# On_Board_Computer.net
KiCad netlist of a schematic drawn in EAGLE
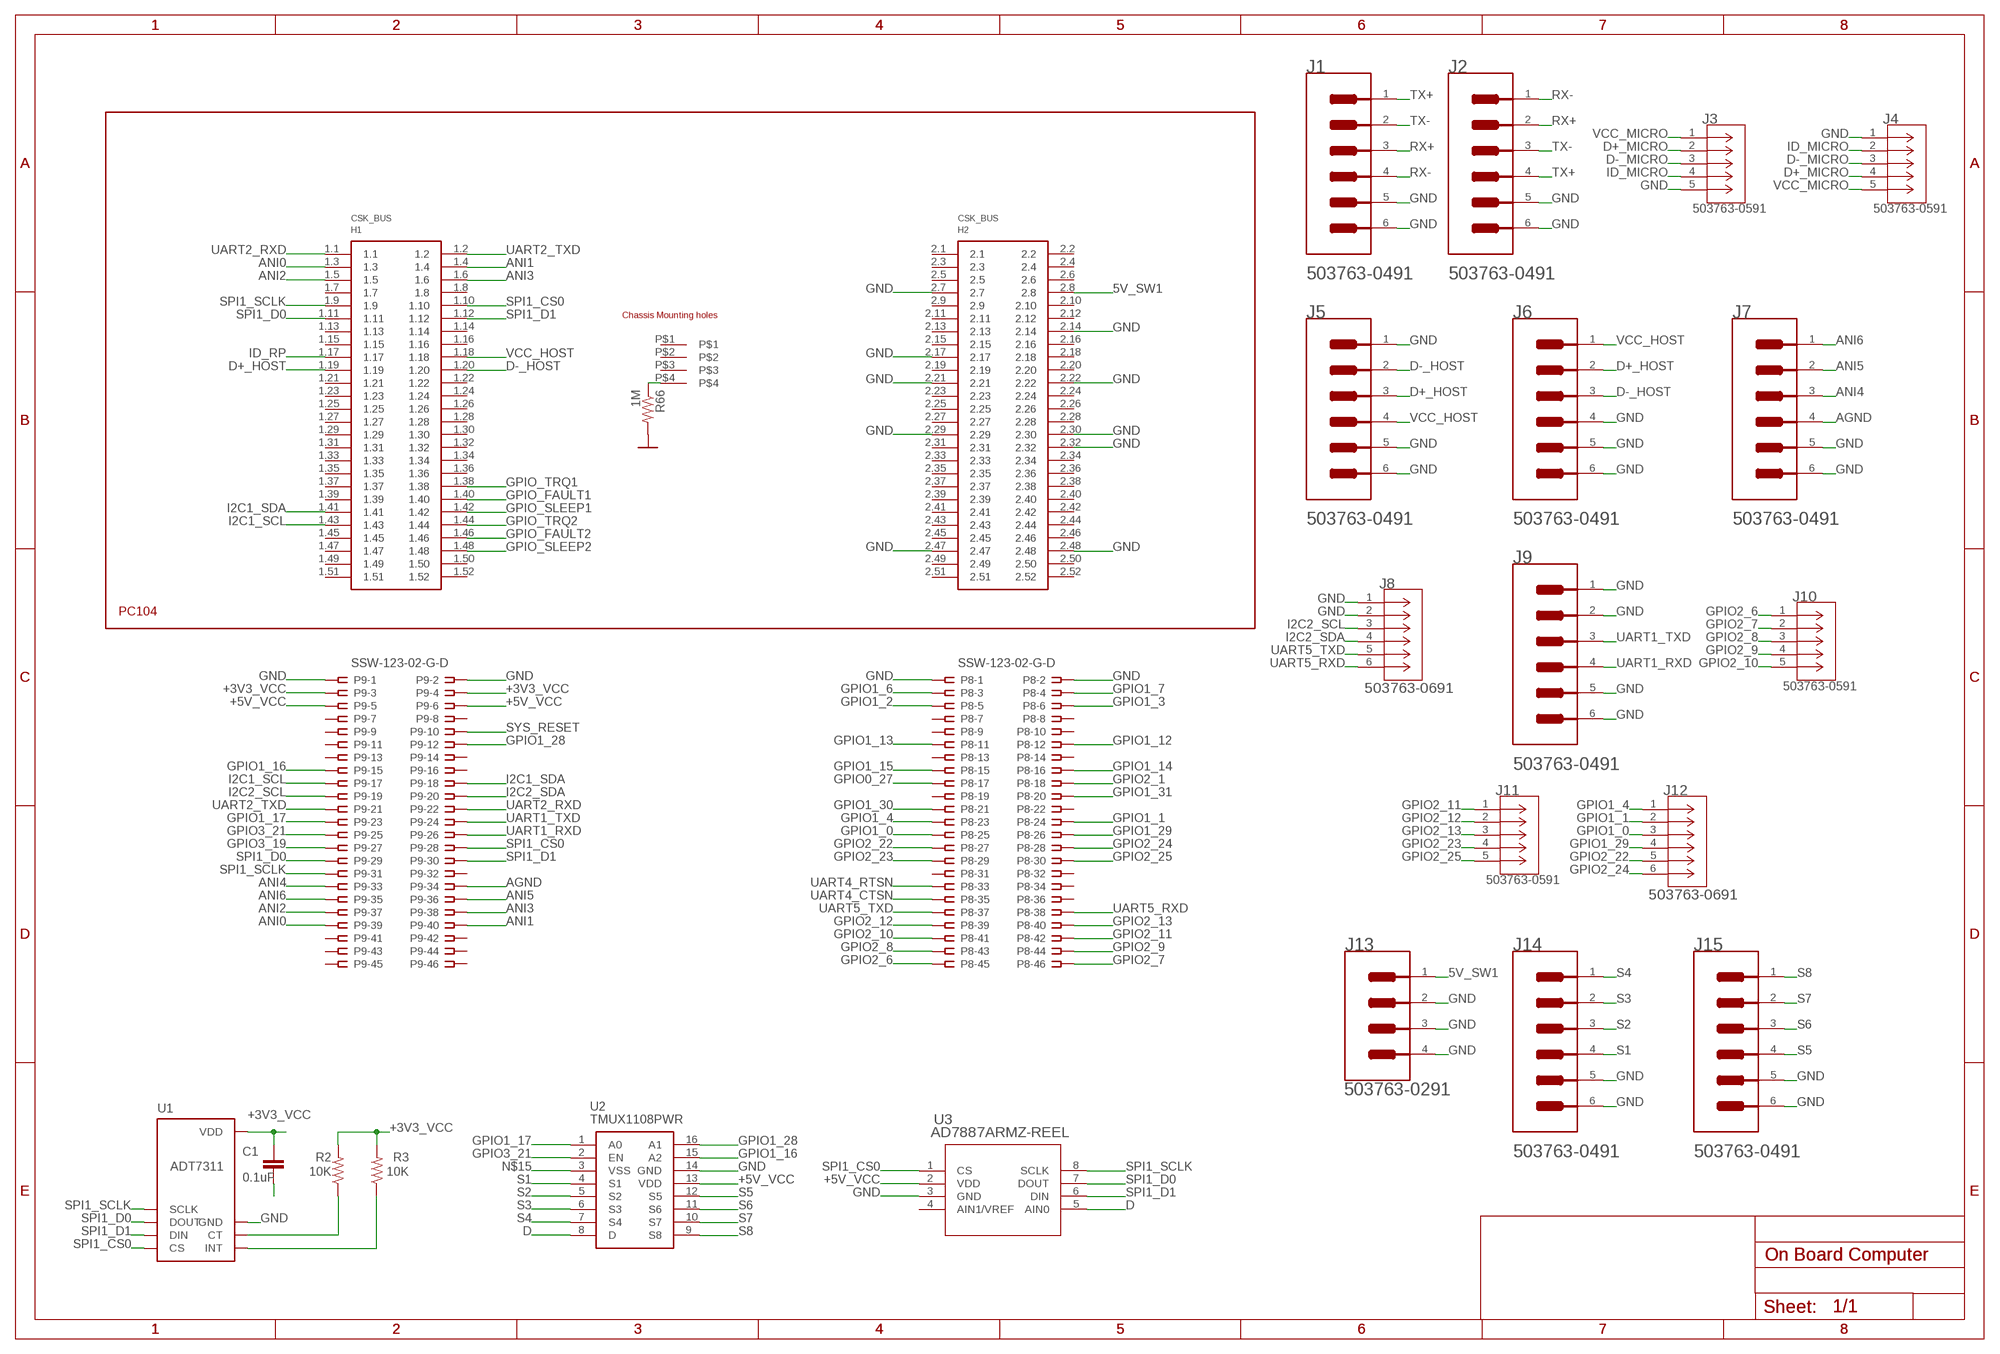
[diagram p0: schematic, sheet 1]

(export (version "E")
  (design (tool "Eeschema 10.0.6"))
  (components
    (comp (ref "C1")
      (value "0.1uF")
      (footprint "eagle-import:0805")
      (libsource (lib "eagle-import") (part "CAP0805"))
    )
    (comp (ref "H1")
      (value "PC104_WCONN")
      (footprint "eagle-import:PC104_WCONN")
      (libsource (lib "eagle-import") (part "PC104_WCONN"))
    )
    (comp (ref "J1")
      (value "MOLEX_503763-0491MOLEX_503763-0491_0_0")
      (footprint "eagle-import:MOLEX_503763-0491_0")
      (fields
        (field (name "DIGIKEY_PART_NUMBER") "WM10655CT-ND")
        (field (name "MF") "Molex")
        (field (name "MOUSER_PART_NUMBER") "538-503763-0491")
      )
      (libsource (lib "eagle-import") (part "MOLEX_503763-0491MOLEX_503763-0491_0_0"))
    )
    (comp (ref "J2")
      (value "MOLEX_503763-0491MOLEX_503763-0491_0_0")
      (footprint "eagle-import:MOLEX_503763-0491_0")
      (fields
        (field (name "DIGIKEY_PART_NUMBER") "WM10655CT-ND")
        (field (name "MF") "Molex")
        (field (name "MOUSER_PART_NUMBER") "538-503763-0491")
      )
      (libsource (lib "eagle-import") (part "MOLEX_503763-0491MOLEX_503763-0491_0_0"))
    )
    (comp (ref "J3")
      (value "503763-0591")
      (footprint "eagle-import:CONN_5037630591_MOL")
      (fields (field (name "COPYRIGHT") "Copyright (C) 2018 Accelerated Designs. All rights reserved"))
      (libsource (lib "eagle-import") (part "503763-0591"))
    )
    (comp (ref "J4")
      (value "503763-0591")
      (footprint "eagle-import:CONN_5037630591_MOL")
      (fields (field (name "COPYRIGHT") "Copyright (C) 2018 Accelerated Designs. All rights reserved"))
      (libsource (lib "eagle-import") (part "503763-0591"))
    )
    (comp (ref "J5")
      (value "MOLEX_503763-0491MOLEX_503763-0491_0_0")
      (footprint "eagle-import:MOLEX_503763-0491_0")
      (fields
        (field (name "DIGIKEY_PART_NUMBER") "WM10655CT-ND")
        (field (name "MF") "Molex")
        (field (name "MOUSER_PART_NUMBER") "538-503763-0491")
      )
      (libsource (lib "eagle-import") (part "MOLEX_503763-0491MOLEX_503763-0491_0_0"))
    )
    (comp (ref "J6")
      (value "MOLEX_503763-0491MOLEX_503763-0491_0_0")
      (footprint "eagle-import:MOLEX_503763-0491_0")
      (fields
        (field (name "DIGIKEY_PART_NUMBER") "WM10655CT-ND")
        (field (name "MF") "Molex")
        (field (name "MOUSER_PART_NUMBER") "538-503763-0491")
      )
      (libsource (lib "eagle-import") (part "MOLEX_503763-0491MOLEX_503763-0491_0_0"))
    )
    (comp (ref "J7")
      (value "MOLEX_503763-0491MOLEX_503763-0491_0_0")
      (footprint "eagle-import:MOLEX_503763-0491_0")
      (fields
        (field (name "DIGIKEY_PART_NUMBER") "WM10655CT-ND")
        (field (name "MF") "Molex")
        (field (name "MOUSER_PART_NUMBER") "538-503763-0491")
      )
      (libsource (lib "eagle-import") (part "MOLEX_503763-0491MOLEX_503763-0491_0_0"))
    )
    (comp (ref "J8")
      (value "503763-0691")
      (footprint "eagle-import:CONN_503763-0691_MOL")
      (fields (field (name "COPYRIGHT") "Copyright (C) 2018 Accelerated Designs. All rights reserved"))
      (libsource (lib "eagle-import") (part "503763-0691"))
    )
    (comp (ref "J9")
      (value "MOLEX_503763-0491MOLEX_503763-0491_0_0")
      (footprint "eagle-import:MOLEX_503763-0491_0")
      (fields
        (field (name "DIGIKEY_PART_NUMBER") "WM10655CT-ND")
        (field (name "MF") "Molex")
        (field (name "MOUSER_PART_NUMBER") "538-503763-0491")
      )
      (libsource (lib "eagle-import") (part "MOLEX_503763-0491MOLEX_503763-0491_0_0"))
    )
    (comp (ref "J10")
      (value "503763-0591")
      (footprint "eagle-import:CONN_5037630591_MOL")
      (fields (field (name "COPYRIGHT") "Copyright (C) 2018 Accelerated Designs. All rights reserved"))
      (libsource (lib "eagle-import") (part "503763-0591"))
    )
    (comp (ref "J11")
      (value "503763-0591")
      (footprint "eagle-import:CONN_5037630591_MOL")
      (fields (field (name "COPYRIGHT") "Copyright (C) 2018 Accelerated Designs. All rights reserved"))
      (libsource (lib "eagle-import") (part "503763-0591"))
    )
    (comp (ref "J12")
      (value "503763-0691")
      (footprint "eagle-import:CONN_503763-0691_MOL")
      (fields (field (name "COPYRIGHT") "Copyright (C) 2018 Accelerated Designs. All rights reserved"))
      (libsource (lib "eagle-import") (part "503763-0691"))
    )
    (comp (ref "J13")
      (value "MOLEX_503763-0291MOLEX_503763-0291_0_0")
      (footprint "eagle-import:MOLEX_503763-0291_0")
      (fields
        (field (name "DIGIKEY_PART_NUMBER") "WM10654CT-ND")
        (field (name "MF") "Molex")
        (field (name "MOUSER_PART_NUMBER") "538-503763-0291")
      )
      (libsource (lib "eagle-import") (part "MOLEX_503763-0291MOLEX_503763-0291_0_0"))
    )
    (comp (ref "J14")
      (value "MOLEX_503763-0491MOLEX_503763-0491_0_0")
      (footprint "eagle-import:MOLEX_503763-0491_0")
      (fields
        (field (name "DIGIKEY_PART_NUMBER") "WM10655CT-ND")
        (field (name "MF") "Molex")
        (field (name "MOUSER_PART_NUMBER") "538-503763-0491")
      )
      (libsource (lib "eagle-import") (part "MOLEX_503763-0491MOLEX_503763-0491_0_0"))
    )
    (comp (ref "J15")
      (value "MOLEX_503763-0491MOLEX_503763-0491_0_0")
      (footprint "eagle-import:MOLEX_503763-0491_0")
      (fields
        (field (name "DIGIKEY_PART_NUMBER") "WM10655CT-ND")
        (field (name "MF") "Molex")
        (field (name "MOUSER_PART_NUMBER") "538-503763-0491")
      )
      (libsource (lib "eagle-import") (part "MOLEX_503763-0491MOLEX_503763-0491_0_0"))
    )
    (comp (ref "P8")
      (value "SSW-123-02-G-D")
      (footprint "eagle-import:SSW-123-02-G-D")
      (fields (field (name "MF") "Samtec Inc."))
      (libsource (lib "eagle-import") (part "SSW-123-02-G-D"))
    )
    (comp (ref "P9")
      (value "SSW-123-02-G-D")
      (footprint "eagle-import:SSW-123-02-G-D")
      (fields (field (name "MF") "Samtec Inc."))
      (libsource (lib "eagle-import") (part "SSW-123-02-G-D"))
    )
    (comp (ref "R2")
      (value "10K")
      (footprint "eagle-import:0805")
      (libsource (lib "eagle-import") (part "RESISTOR0805-RES"))
    )
    (comp (ref "R3")
      (value "10K")
      (footprint "eagle-import:0805")
      (libsource (lib "eagle-import") (part "RESISTOR0805-RES"))
    )
    (comp (ref "R66")
      (value "1M")
      (footprint "eagle-import:0805")
      (libsource (lib "eagle-import") (part "RESISTOR0805-RES"))
    )
    (comp (ref "U1")
      (value "ADT7311")
      (footprint "eagle-import:SOIC-8")
      (libsource (lib "eagle-import") (part "ADT7311"))
    )
    (comp (ref "U2")
      (value "TMUX1108PWR")
      (footprint "eagle-import:SOP65P640X120-16N")
      (fields (field (name "MOUSER_PART_NUMBER") "595-TMUX1108PWR"))
      (libsource (lib "eagle-import") (part "TMUX1108PWR"))
    )
    (comp (ref "U3")
      (value "AD7887ARMZ-REEL")
      (footprint "eagle-import:RM_8_ADI")
      (libsource (lib "eagle-import") (part "AD7887ARMZ-REEL"))
    )
  )
  (nets
    (net (code "1") (name "/+3V3_VCC") (class "Default")
      (node (ref "C1") (pin "1") (pinfunction "1_1") (pintype "passive"))
      (node (ref "P9") (pin "3") (pinfunction "1_3") (pintype "passive"))
      (node (ref "P9") (pin "4") (pinfunction "1_4") (pintype "passive"))
      (node (ref "R2") (pin "2") (pinfunction "2_2") (pintype "passive"))
      (node (ref "R3") (pin "2") (pinfunction "2_2") (pintype "passive"))
      (node (ref "U1") (pin "8") (pinfunction "VDD_8") (pintype "bidirectional"))
    )
    (net (code "2") (name "/+5V_VCC") (class "Default")
      (node (ref "P9") (pin "5") (pinfunction "1_5") (pintype "passive"))
      (node (ref "P9") (pin "6") (pinfunction "1_6") (pintype "passive"))
      (node (ref "U2") (pin "13") (pinfunction "VDD_13") (pintype "bidirectional"))
      (node (ref "U3") (pin "2") (pinfunction "VDD_2") (pintype "power_in"))
    )
    (net (code "3") (name "/5V_SW1") (class "Default")
      (node (ref "H1") (pin "2.8") (pinfunction "2.8_2.8") (pintype "bidirectional"))
      (node (ref "J13") (pin "1") (pinfunction "1_1") (pintype "bidirectional"))
    )
    (net (code "4") (name "/AGND") (class "Default")
      (node (ref "J7") (pin "4") (pinfunction "4_4") (pintype "passive"))
      (node (ref "P9") (pin "34") (pinfunction "1_34") (pintype "passive"))
    )
    (net (code "5") (name "/ANI0") (class "Default")
      (node (ref "H1") (pin "1.3") (pinfunction "1.3_1.3") (pintype "bidirectional"))
      (node (ref "P9") (pin "39") (pinfunction "1_39") (pintype "passive"))
    )
    (net (code "6") (name "/ANI1") (class "Default")
      (node (ref "H1") (pin "1.4") (pinfunction "1.4_1.4") (pintype "bidirectional"))
      (node (ref "P9") (pin "40") (pinfunction "1_40") (pintype "passive"))
    )
    (net (code "7") (name "/ANI2") (class "Default")
      (node (ref "H1") (pin "1.5") (pinfunction "1.5_1.5") (pintype "bidirectional"))
      (node (ref "P9") (pin "37") (pinfunction "1_37") (pintype "passive"))
    )
    (net (code "8") (name "/ANI3") (class "Default")
      (node (ref "H1") (pin "1.6") (pinfunction "1.6_1.6") (pintype "bidirectional"))
      (node (ref "P9") (pin "38") (pinfunction "1_38") (pintype "passive"))
    )
    (net (code "9") (name "/ANI4") (class "Default")
      (node (ref "J7") (pin "3") (pinfunction "3_3") (pintype "passive"))
      (node (ref "P9") (pin "33") (pinfunction "1_33") (pintype "passive"))
    )
    (net (code "10") (name "/ANI5") (class "Default")
      (node (ref "J7") (pin "2") (pinfunction "2_2") (pintype "passive"))
      (node (ref "P9") (pin "36") (pinfunction "1_36") (pintype "passive"))
    )
    (net (code "11") (name "/ANI6") (class "Default")
      (node (ref "J7") (pin "1") (pinfunction "1_1") (pintype "passive"))
      (node (ref "P9") (pin "35") (pinfunction "1_35") (pintype "passive"))
    )
    (net (code "12") (name "/D") (class "Default")
      (node (ref "U2") (pin "8") (pinfunction "D_8") (pintype "bidirectional"))
      (node (ref "U3") (pin "5") (pinfunction "AIN0_5") (pintype "passive"))
    )
    (net (code "13") (name "/D+_HOST") (class "Default")
      (node (ref "H1") (pin "1.19") (pinfunction "1.19_1.19") (pintype "bidirectional"))
      (node (ref "J5") (pin "3") (pinfunction "3_3") (pintype "passive"))
      (node (ref "J6") (pin "2") (pinfunction "2_2") (pintype "passive"))
    )
    (net (code "14") (name "/D+_MICRO") (class "Default")
      (node (ref "J3") (pin "2") (pinfunction "2_2") (pintype "passive"))
      (node (ref "J4") (pin "4") (pinfunction "4_4") (pintype "passive"))
    )
    (net (code "15") (name "/D-_HOST") (class "Default")
      (node (ref "H1") (pin "1.20") (pinfunction "1.20_1.20") (pintype "bidirectional"))
      (node (ref "J5") (pin "2") (pinfunction "2_2") (pintype "passive"))
      (node (ref "J6") (pin "3") (pinfunction "3_3") (pintype "passive"))
    )
    (net (code "16") (name "/D-_MICRO") (class "Default")
      (node (ref "J3") (pin "3") (pinfunction "3_3") (pintype "passive"))
      (node (ref "J4") (pin "3") (pinfunction "3_3") (pintype "passive"))
    )
    (net (code "17") (name "/GPIO0_27") (class "Default")
      (node (ref "P8") (pin "17") (pinfunction "1_17") (pintype "passive"))
    )
    (net (code "18") (name "/GPIO1_0") (class "Default")
      (node (ref "J12") (pin "3") (pinfunction "3_3") (pintype "passive"))
      (node (ref "P8") (pin "25") (pinfunction "1_25") (pintype "passive"))
    )
    (net (code "19") (name "/GPIO1_1") (class "Default")
      (node (ref "J12") (pin "2") (pinfunction "2_2") (pintype "passive"))
      (node (ref "P8") (pin "24") (pinfunction "1_24") (pintype "passive"))
    )
    (net (code "20") (name "/GPIO1_2") (class "Default")
      (node (ref "P8") (pin "5") (pinfunction "1_5") (pintype "passive"))
    )
    (net (code "21") (name "/GPIO1_3") (class "Default")
      (node (ref "P8") (pin "6") (pinfunction "1_6") (pintype "passive"))
    )
    (net (code "22") (name "/GPIO1_4") (class "Default")
      (node (ref "J12") (pin "1") (pinfunction "1_1") (pintype "passive"))
      (node (ref "P8") (pin "23") (pinfunction "1_23") (pintype "passive"))
    )
    (net (code "23") (name "/GPIO1_6") (class "Default")
      (node (ref "P8") (pin "3") (pinfunction "1_3") (pintype "passive"))
    )
    (net (code "24") (name "/GPIO1_7") (class "Default")
      (node (ref "P8") (pin "4") (pinfunction "1_4") (pintype "passive"))
    )
    (net (code "25") (name "/GPIO1_12") (class "Default")
      (node (ref "P8") (pin "12") (pinfunction "1_12") (pintype "passive"))
    )
    (net (code "26") (name "/GPIO1_13") (class "Default")
      (node (ref "P8") (pin "11") (pinfunction "1_11") (pintype "passive"))
    )
    (net (code "27") (name "/GPIO1_14") (class "Default")
      (node (ref "P8") (pin "16") (pinfunction "1_16") (pintype "passive"))
    )
    (net (code "28") (name "/GPIO1_15") (class "Default")
      (node (ref "P8") (pin "15") (pinfunction "1_15") (pintype "passive"))
    )
    (net (code "29") (name "/GPIO1_16") (class "Default")
      (node (ref "P9") (pin "15") (pinfunction "1_15") (pintype "passive"))
      (node (ref "U2") (pin "15") (pinfunction "A2_15") (pintype "bidirectional"))
    )
    (net (code "30") (name "/GPIO1_17") (class "Default")
      (node (ref "P9") (pin "23") (pinfunction "1_23") (pintype "passive"))
      (node (ref "U2") (pin "1") (pinfunction "A0_1") (pintype "bidirectional"))
    )
    (net (code "31") (name "/GPIO1_28") (class "Default")
      (node (ref "P9") (pin "12") (pinfunction "1_12") (pintype "passive"))
      (node (ref "U2") (pin "16") (pinfunction "A1_16") (pintype "bidirectional"))
    )
    (net (code "32") (name "/GPIO1_29") (class "Default")
      (node (ref "J12") (pin "4") (pinfunction "4_4") (pintype "passive"))
      (node (ref "P8") (pin "26") (pinfunction "1_26") (pintype "passive"))
    )
    (net (code "33") (name "/GPIO1_30") (class "Default")
      (node (ref "P8") (pin "21") (pinfunction "1_21") (pintype "passive"))
    )
    (net (code "34") (name "/GPIO1_31") (class "Default")
      (node (ref "P8") (pin "20") (pinfunction "1_20") (pintype "passive"))
    )
    (net (code "35") (name "/GPIO2_1") (class "Default")
      (node (ref "P8") (pin "18") (pinfunction "1_18") (pintype "passive"))
    )
    (net (code "36") (name "/GPIO2_6") (class "Default")
      (node (ref "J10") (pin "1") (pinfunction "1_1") (pintype "passive"))
      (node (ref "P8") (pin "45") (pinfunction "1_45") (pintype "passive"))
    )
    (net (code "37") (name "/GPIO2_7") (class "Default")
      (node (ref "J10") (pin "2") (pinfunction "2_2") (pintype "passive"))
      (node (ref "P8") (pin "46") (pinfunction "1_46") (pintype "passive"))
    )
    (net (code "38") (name "/GPIO2_8") (class "Default")
      (node (ref "J10") (pin "3") (pinfunction "3_3") (pintype "passive"))
      (node (ref "P8") (pin "43") (pinfunction "1_43") (pintype "passive"))
    )
    (net (code "39") (name "/GPIO2_9") (class "Default")
      (node (ref "J10") (pin "4") (pinfunction "4_4") (pintype "passive"))
      (node (ref "P8") (pin "44") (pinfunction "1_44") (pintype "passive"))
    )
    (net (code "40") (name "/GPIO2_10") (class "Default")
      (node (ref "J10") (pin "5") (pinfunction "5_5") (pintype "passive"))
      (node (ref "P8") (pin "41") (pinfunction "1_41") (pintype "passive"))
    )
    (net (code "41") (name "/GPIO2_11") (class "Default")
      (node (ref "J11") (pin "1") (pinfunction "1_1") (pintype "passive"))
      (node (ref "P8") (pin "42") (pinfunction "1_42") (pintype "passive"))
    )
    (net (code "42") (name "/GPIO2_12") (class "Default")
      (node (ref "J11") (pin "2") (pinfunction "2_2") (pintype "passive"))
      (node (ref "P8") (pin "39") (pinfunction "1_39") (pintype "passive"))
    )
    (net (code "43") (name "/GPIO2_13") (class "Default")
      (node (ref "J11") (pin "3") (pinfunction "3_3") (pintype "passive"))
      (node (ref "P8") (pin "40") (pinfunction "1_40") (pintype "passive"))
    )
    (net (code "44") (name "/GPIO2_22") (class "Default")
      (node (ref "J12") (pin "5") (pinfunction "5_5") (pintype "passive"))
      (node (ref "P8") (pin "27") (pinfunction "1_27") (pintype "passive"))
    )
    (net (code "45") (name "/GPIO2_23") (class "Default")
      (node (ref "J11") (pin "4") (pinfunction "4_4") (pintype "passive"))
      (node (ref "P8") (pin "29") (pinfunction "1_29") (pintype "passive"))
    )
    (net (code "46") (name "/GPIO2_24") (class "Default")
      (node (ref "J12") (pin "6") (pinfunction "6_6") (pintype "passive"))
      (node (ref "P8") (pin "28") (pinfunction "1_28") (pintype "passive"))
    )
    (net (code "47") (name "/GPIO2_25") (class "Default")
      (node (ref "J11") (pin "5") (pinfunction "5_5") (pintype "passive"))
      (node (ref "P8") (pin "30") (pinfunction "1_30") (pintype "passive"))
    )
    (net (code "48") (name "/GPIO3_19") (class "Default")
      (node (ref "P9") (pin "27") (pinfunction "1_27") (pintype "passive"))
    )
    (net (code "49") (name "/GPIO3_21") (class "Default")
      (node (ref "P9") (pin "25") (pinfunction "1_25") (pintype "passive"))
      (node (ref "U2") (pin "2") (pinfunction "EN_2") (pintype "bidirectional"))
    )
    (net (code "50") (name "/GPIO_FAULT1") (class "Default")
      (node (ref "H1") (pin "1.40") (pinfunction "1.40_1.40") (pintype "bidirectional"))
    )
    (net (code "51") (name "/GPIO_FAULT2") (class "Default")
      (node (ref "H1") (pin "1.46") (pinfunction "1.46_1.46") (pintype "bidirectional"))
    )
    (net (code "52") (name "/GPIO_SLEEP1") (class "Default")
      (node (ref "H1") (pin "1.42") (pinfunction "1.42_1.42") (pintype "bidirectional"))
    )
    (net (code "53") (name "/GPIO_SLEEP2") (class "Default")
      (node (ref "H1") (pin "1.48") (pinfunction "1.48_1.48") (pintype "bidirectional"))
    )
    (net (code "54") (name "/GPIO_TRQ1") (class "Default")
      (node (ref "H1") (pin "1.38") (pinfunction "1.38_1.38") (pintype "bidirectional"))
    )
    (net (code "55") (name "/GPIO_TRQ2") (class "Default")
      (node (ref "H1") (pin "1.44") (pinfunction "1.44_1.44") (pintype "bidirectional"))
    )
    (net (code "56") (name "/I2C1_SCL") (class "Default")
      (node (ref "H1") (pin "1.43") (pinfunction "1.43_1.43") (pintype "bidirectional"))
      (node (ref "P9") (pin "17") (pinfunction "1_17") (pintype "passive"))
    )
    (net (code "57") (name "/I2C1_SDA") (class "Default")
      (node (ref "H1") (pin "1.41") (pinfunction "1.41_1.41") (pintype "bidirectional"))
      (node (ref "P9") (pin "18") (pinfunction "1_18") (pintype "passive"))
    )
    (net (code "58") (name "/I2C2_SCL") (class "Default")
      (node (ref "J8") (pin "3") (pinfunction "3_3") (pintype "passive"))
      (node (ref "P9") (pin "19") (pinfunction "1_19") (pintype "passive"))
    )
    (net (code "59") (name "/I2C2_SDA") (class "Default")
      (node (ref "J8") (pin "4") (pinfunction "4_4") (pintype "passive"))
      (node (ref "P9") (pin "20") (pinfunction "1_20") (pintype "passive"))
    )
    (net (code "60") (name "/ID_MICRO") (class "Default")
      (node (ref "J3") (pin "4") (pinfunction "4_4") (pintype "passive"))
      (node (ref "J4") (pin "2") (pinfunction "2_2") (pintype "passive"))
    )
    (net (code "61") (name "/ID_RP") (class "Default")
      (node (ref "H1") (pin "1.17") (pinfunction "1.17_1.17") (pintype "bidirectional"))
    )
    (net (code "62") (name "/N$15") (class "Default")
      (node (ref "U2") (pin "3") (pinfunction "VSS_3") (pintype "bidirectional"))
    )
    (net (code "63") (name "/RX+") (class "Default")
      (node (ref "J1") (pin "3") (pinfunction "3_3") (pintype "passive"))
      (node (ref "J2") (pin "2") (pinfunction "2_2") (pintype "passive"))
    )
    (net (code "64") (name "/RX-") (class "Default")
      (node (ref "J1") (pin "4") (pinfunction "4_4") (pintype "passive"))
      (node (ref "J2") (pin "1") (pinfunction "1_1") (pintype "passive"))
    )
    (net (code "65") (name "/S1") (class "Default")
      (node (ref "J14") (pin "4") (pinfunction "4_4") (pintype "passive"))
      (node (ref "U2") (pin "4") (pinfunction "S1_4") (pintype "bidirectional"))
    )
    (net (code "66") (name "/S2") (class "Default")
      (node (ref "J14") (pin "3") (pinfunction "3_3") (pintype "passive"))
      (node (ref "U2") (pin "5") (pinfunction "S2_5") (pintype "bidirectional"))
    )
    (net (code "67") (name "/S3") (class "Default")
      (node (ref "J14") (pin "2") (pinfunction "2_2") (pintype "passive"))
      (node (ref "U2") (pin "6") (pinfunction "S3_6") (pintype "bidirectional"))
    )
    (net (code "68") (name "/S4") (class "Default")
      (node (ref "J14") (pin "1") (pinfunction "1_1") (pintype "passive"))
      (node (ref "U2") (pin "7") (pinfunction "S4_7") (pintype "bidirectional"))
    )
    (net (code "69") (name "/S5") (class "Default")
      (node (ref "J15") (pin "4") (pinfunction "4_4") (pintype "passive"))
      (node (ref "U2") (pin "12") (pinfunction "S5_12") (pintype "bidirectional"))
    )
    (net (code "70") (name "/S6") (class "Default")
      (node (ref "J15") (pin "3") (pinfunction "3_3") (pintype "passive"))
      (node (ref "U2") (pin "11") (pinfunction "S6_11") (pintype "bidirectional"))
    )
    (net (code "71") (name "/S7") (class "Default")
      (node (ref "J15") (pin "2") (pinfunction "2_2") (pintype "passive"))
      (node (ref "U2") (pin "10") (pinfunction "S7_10") (pintype "bidirectional"))
    )
    (net (code "72") (name "/S8") (class "Default")
      (node (ref "J15") (pin "1") (pinfunction "1_1") (pintype "passive"))
      (node (ref "U2") (pin "9") (pinfunction "S8_9") (pintype "bidirectional"))
    )
    (net (code "73") (name "/SPI1_CS0") (class "Default")
      (node (ref "H1") (pin "1.10") (pinfunction "1.10_1.10") (pintype "bidirectional"))
      (node (ref "P9") (pin "28") (pinfunction "1_28") (pintype "passive"))
      (node (ref "U1") (pin "4") (pinfunction "CS_4") (pintype "bidirectional"))
      (node (ref "U3") (pin "1") (pinfunction "CS_1") (pintype "passive"))
    )
    (net (code "74") (name "/SPI1_D0") (class "Default")
      (node (ref "H1") (pin "1.11") (pinfunction "1.11_1.11") (pintype "bidirectional"))
      (node (ref "P9") (pin "29") (pinfunction "1_29") (pintype "passive"))
      (node (ref "U1") (pin "2") (pinfunction "DOUT_2") (pintype "bidirectional"))
      (node (ref "U3") (pin "7") (pinfunction "DOUT_7") (pintype "passive"))
    )
    (net (code "75") (name "/SPI1_D1") (class "Default")
      (node (ref "H1") (pin "1.12") (pinfunction "1.12_1.12") (pintype "bidirectional"))
      (node (ref "P9") (pin "30") (pinfunction "1_30") (pintype "passive"))
      (node (ref "U1") (pin "3") (pinfunction "DIN_3") (pintype "bidirectional"))
      (node (ref "U3") (pin "6") (pinfunction "DIN_6") (pintype "passive"))
    )
    (net (code "76") (name "/SPI1_SCLK") (class "Default")
      (node (ref "H1") (pin "1.9") (pinfunction "1.9_1.9") (pintype "bidirectional"))
      (node (ref "P9") (pin "31") (pinfunction "1_31") (pintype "passive"))
      (node (ref "U1") (pin "1") (pinfunction "SCLK_1") (pintype "bidirectional"))
      (node (ref "U3") (pin "8") (pinfunction "SCLK_8") (pintype "passive"))
    )
    (net (code "77") (name "/SYS_RESET") (class "Default")
      (node (ref "P9") (pin "10") (pinfunction "1_10") (pintype "passive"))
    )
    (net (code "78") (name "/TX+") (class "Default")
      (node (ref "J1") (pin "1") (pinfunction "1_1") (pintype "passive"))
      (node (ref "J2") (pin "4") (pinfunction "4_4") (pintype "passive"))
    )
    (net (code "79") (name "/TX-") (class "Default")
      (node (ref "J1") (pin "2") (pinfunction "2_2") (pintype "passive"))
      (node (ref "J2") (pin "3") (pinfunction "3_3") (pintype "passive"))
    )
    (net (code "80") (name "/UART1_RXD") (class "Default")
      (node (ref "J9") (pin "4") (pinfunction "4_4") (pintype "passive"))
      (node (ref "P9") (pin "26") (pinfunction "1_26") (pintype "passive"))
    )
    (net (code "81") (name "/UART1_TXD") (class "Default")
      (node (ref "J9") (pin "3") (pinfunction "3_3") (pintype "passive"))
      (node (ref "P9") (pin "24") (pinfunction "1_24") (pintype "passive"))
    )
    (net (code "82") (name "/UART2_RXD") (class "Default")
      (node (ref "H1") (pin "1.1") (pinfunction "1.1_1.1") (pintype "bidirectional"))
      (node (ref "P9") (pin "22") (pinfunction "1_22") (pintype "passive"))
    )
    (net (code "83") (name "/UART2_TXD") (class "Default")
      (node (ref "H1") (pin "1.2") (pinfunction "1.2_1.2") (pintype "bidirectional"))
      (node (ref "P9") (pin "21") (pinfunction "1_21") (pintype "passive"))
    )
    (net (code "84") (name "/UART4_CTSN") (class "Default")
      (node (ref "P8") (pin "35") (pinfunction "1_35") (pintype "passive"))
    )
    (net (code "85") (name "/UART4_RTSN") (class "Default")
      (node (ref "P8") (pin "33") (pinfunction "1_33") (pintype "passive"))
    )
    (net (code "86") (name "/UART5_RXD") (class "Default")
      (node (ref "J8") (pin "6") (pinfunction "6_6") (pintype "passive"))
      (node (ref "P8") (pin "38") (pinfunction "1_38") (pintype "passive"))
    )
    (net (code "87") (name "/UART5_TXD") (class "Default")
      (node (ref "J8") (pin "5") (pinfunction "5_5") (pintype "passive"))
      (node (ref "P8") (pin "37") (pinfunction "1_37") (pintype "passive"))
    )
    (net (code "88") (name "/VCC_HOST") (class "Default")
      (node (ref "H1") (pin "1.18") (pinfunction "1.18_1.18") (pintype "bidirectional"))
      (node (ref "J5") (pin "4") (pinfunction "4_4") (pintype "passive"))
      (node (ref "J6") (pin "1") (pinfunction "1_1") (pintype "passive"))
    )
    (net (code "89") (name "/VCC_MICRO") (class "Default")
      (node (ref "J3") (pin "1") (pinfunction "1_1") (pintype "passive"))
      (node (ref "J4") (pin "5") (pinfunction "5_5") (pintype "passive"))
    )
    (net (code "90") (name "GND") (class "Default")
      (node (ref "C1") (pin "2") (pinfunction "2_2") (pintype "passive"))
      (node (ref "H1") (pin "2.14") (pinfunction "2.14_2.14") (pintype "bidirectional"))
      (node (ref "H1") (pin "2.17") (pinfunction "2.17_2.17") (pintype "bidirectional"))
      (node (ref "H1") (pin "2.21") (pinfunction "2.21_2.21") (pintype "bidirectional"))
      (node (ref "H1") (pin "2.22") (pinfunction "2.22_2.22") (pintype "bidirectional"))
      (node (ref "H1") (pin "2.29") (pinfunction "2.29_2.29") (pintype "bidirectional"))
      (node (ref "H1") (pin "2.30") (pinfunction "2.30_2.30") (pintype "bidirectional"))
      (node (ref "H1") (pin "2.32") (pinfunction "2.32_2.32") (pintype "bidirectional"))
      (node (ref "H1") (pin "2.47") (pinfunction "2.47_2.47") (pintype "bidirectional"))
      (node (ref "H1") (pin "2.48") (pinfunction "2.48_2.48") (pintype "bidirectional"))
      (node (ref "H1") (pin "2.7") (pinfunction "2.7_2.7") (pintype "bidirectional"))
      (node (ref "J1") (pin "5") (pinfunction "MNT_1_5") (pintype "passive"))
      (node (ref "J1") (pin "6") (pinfunction "MNT_2_6") (pintype "passive"))
      (node (ref "J13") (pin "2") (pinfunction "2_2") (pintype "bidirectional"))
      (node (ref "J13") (pin "3") (pinfunction "MNT_1_3") (pintype "bidirectional"))
      (node (ref "J13") (pin "4") (pinfunction "MNT_2_4") (pintype "bidirectional"))
      (node (ref "J14") (pin "5") (pinfunction "MNT_1_5") (pintype "passive"))
      (node (ref "J14") (pin "6") (pinfunction "MNT_2_6") (pintype "passive"))
      (node (ref "J15") (pin "5") (pinfunction "MNT_1_5") (pintype "passive"))
      (node (ref "J15") (pin "6") (pinfunction "MNT_2_6") (pintype "passive"))
      (node (ref "J2") (pin "5") (pinfunction "MNT_1_5") (pintype "passive"))
      (node (ref "J2") (pin "6") (pinfunction "MNT_2_6") (pintype "passive"))
      (node (ref "J3") (pin "5") (pinfunction "5_5") (pintype "passive"))
      (node (ref "J4") (pin "1") (pinfunction "1_1") (pintype "passive"))
      (node (ref "J5") (pin "1") (pinfunction "1_1") (pintype "passive"))
      (node (ref "J5") (pin "5") (pinfunction "MNT_1_5") (pintype "passive"))
      (node (ref "J5") (pin "6") (pinfunction "MNT_2_6") (pintype "passive"))
      (node (ref "J6") (pin "4") (pinfunction "4_4") (pintype "passive"))
      (node (ref "J6") (pin "5") (pinfunction "MNT_1_5") (pintype "passive"))
      (node (ref "J6") (pin "6") (pinfunction "MNT_2_6") (pintype "passive"))
      (node (ref "J7") (pin "5") (pinfunction "MNT_1_5") (pintype "passive"))
      (node (ref "J7") (pin "6") (pinfunction "MNT_2_6") (pintype "passive"))
      (node (ref "J8") (pin "1") (pinfunction "1_1") (pintype "passive"))
      (node (ref "J8") (pin "2") (pinfunction "2_2") (pintype "passive"))
      (node (ref "J9") (pin "1") (pinfunction "1_1") (pintype "passive"))
      (node (ref "J9") (pin "2") (pinfunction "2_2") (pintype "passive"))
      (node (ref "J9") (pin "5") (pinfunction "MNT_1_5") (pintype "passive"))
      (node (ref "J9") (pin "6") (pinfunction "MNT_2_6") (pintype "passive"))
      (node (ref "P8") (pin "1") (pinfunction "1_1") (pintype "passive"))
      (node (ref "P8") (pin "2") (pinfunction "1_2") (pintype "passive"))
      (node (ref "P9") (pin "1") (pinfunction "1_1") (pintype "passive"))
      (node (ref "P9") (pin "2") (pinfunction "1_2") (pintype "passive"))
      (node (ref "R66") (pin "2") (pinfunction "2_2") (pintype "passive"))
      (node (ref "U1") (pin "7") (pinfunction "GND_7") (pintype "bidirectional"))
      (node (ref "U2") (pin "14") (pinfunction "GND_14") (pintype "bidirectional"))
      (node (ref "U3") (pin "3") (pinfunction "GND_3") (pintype "passive"))
    )
    (net (code "91") (name "Net-(H1-PadP$4)") (class "Default")
      (node (ref "H1") (pin "P$4") (pinfunction "P$4_P$4") (pintype "bidirectional"))
      (node (ref "R66") (pin "1") (pinfunction "1_1") (pintype "passive"))
    )
    (net (code "92") (name "Net-(U1-CT)") (class "Default")
      (node (ref "R2") (pin "1") (pinfunction "1_1") (pintype "passive"))
      (node (ref "U1") (pin "6") (pinfunction "CT_6") (pintype "bidirectional"))
    )
    (net (code "93") (name "Net-(U1-INT)") (class "Default")
      (node (ref "R3") (pin "1") (pinfunction "1_1") (pintype "passive"))
      (node (ref "U1") (pin "5") (pinfunction "INT_5") (pintype "bidirectional"))
    )
    (net (code "94") (name "unconnected-(H1-Pad1.7)") (class "Default")
      (node (ref "H1") (pin "1.7") (pinfunction "1.7_1.7") (pintype "bidirectional"))
    )
    (net (code "95") (name "unconnected-(H1-Pad1.8)") (class "Default")
      (node (ref "H1") (pin "1.8") (pinfunction "1.8_1.8") (pintype "bidirectional"))
    )
    (net (code "96") (name "unconnected-(H1-Pad1.13)") (class "Default")
      (node (ref "H1") (pin "1.13") (pinfunction "1.13_1.13") (pintype "bidirectional"))
    )
    (net (code "97") (name "unconnected-(H1-Pad1.14)") (class "Default")
      (node (ref "H1") (pin "1.14") (pinfunction "1.14_1.14") (pintype "bidirectional"))
    )
    (net (code "98") (name "unconnected-(H1-Pad1.15)") (class "Default")
      (node (ref "H1") (pin "1.15") (pinfunction "1.15_1.15") (pintype "bidirectional"))
    )
    (net (code "99") (name "unconnected-(H1-Pad1.16)") (class "Default")
      (node (ref "H1") (pin "1.16") (pinfunction "1.16_1.16") (pintype "bidirectional"))
    )
    (net (code "100") (name "unconnected-(H1-Pad1.21)") (class "Default")
      (node (ref "H1") (pin "1.21") (pinfunction "1.21_1.21") (pintype "bidirectional"))
    )
    (net (code "101") (name "unconnected-(H1-Pad1.22)") (class "Default")
      (node (ref "H1") (pin "1.22") (pinfunction "1.22_1.22") (pintype "bidirectional"))
    )
    (net (code "102") (name "unconnected-(H1-Pad1.23)") (class "Default")
      (node (ref "H1") (pin "1.23") (pinfunction "1.23_1.23") (pintype "bidirectional"))
    )
    (net (code "103") (name "unconnected-(H1-Pad1.24)") (class "Default")
      (node (ref "H1") (pin "1.24") (pinfunction "1.24_1.24") (pintype "bidirectional"))
    )
    (net (code "104") (name "unconnected-(H1-Pad1.25)") (class "Default")
      (node (ref "H1") (pin "1.25") (pinfunction "1.25_1.25") (pintype "bidirectional"))
    )
    (net (code "105") (name "unconnected-(H1-Pad1.26)") (class "Default")
      (node (ref "H1") (pin "1.26") (pinfunction "1.26_1.26") (pintype "bidirectional"))
    )
    (net (code "106") (name "unconnected-(H1-Pad1.27)") (class "Default")
      (node (ref "H1") (pin "1.27") (pinfunction "1.27_1.27") (pintype "bidirectional"))
    )
    (net (code "107") (name "unconnected-(H1-Pad1.28)") (class "Default")
      (node (ref "H1") (pin "1.28") (pinfunction "1.28_1.28") (pintype "bidirectional"))
    )
    (net (code "108") (name "unconnected-(H1-Pad1.29)") (class "Default")
      (node (ref "H1") (pin "1.29") (pinfunction "1.29_1.29") (pintype "bidirectional"))
    )
    (net (code "109") (name "unconnected-(H1-Pad1.30)") (class "Default")
      (node (ref "H1") (pin "1.30") (pinfunction "1.30_1.30") (pintype "bidirectional"))
    )
    (net (code "110") (name "unconnected-(H1-Pad1.31)") (class "Default")
      (node (ref "H1") (pin "1.31") (pinfunction "1.31_1.31") (pintype "bidirectional"))
    )
    (net (code "111") (name "unconnected-(H1-Pad1.32)") (class "Default")
      (node (ref "H1") (pin "1.32") (pinfunction "1.32_1.32") (pintype "bidirectional"))
    )
    (net (code "112") (name "unconnected-(H1-Pad1.33)") (class "Default")
      (node (ref "H1") (pin "1.33") (pinfunction "1.33_1.33") (pintype "bidirectional"))
    )
    (net (code "113") (name "unconnected-(H1-Pad1.34)") (class "Default")
      (node (ref "H1") (pin "1.34") (pinfunction "1.34_1.34") (pintype "bidirectional"))
    )
    (net (code "114") (name "unconnected-(H1-Pad1.35)") (class "Default")
      (node (ref "H1") (pin "1.35") (pinfunction "1.35_1.35") (pintype "bidirectional"))
    )
    (net (code "115") (name "unconnected-(H1-Pad1.36)") (class "Default")
      (node (ref "H1") (pin "1.36") (pinfunction "1.36_1.36") (pintype "bidirectional"))
    )
    (net (code "116") (name "unconnected-(H1-Pad1.37)") (class "Default")
      (node (ref "H1") (pin "1.37") (pinfunction "1.37_1.37") (pintype "bidirectional"))
    )
    (net (code "117") (name "unconnected-(H1-Pad1.39)") (class "Default")
      (node (ref "H1") (pin "1.39") (pinfunction "1.39_1.39") (pintype "bidirectional"))
    )
    (net (code "118") (name "unconnected-(H1-Pad1.45)") (class "Default")
      (node (ref "H1") (pin "1.45") (pinfunction "1.45_1.45") (pintype "bidirectional"))
    )
    (net (code "119") (name "unconnected-(H1-Pad1.47)") (class "Default")
      (node (ref "H1") (pin "1.47") (pinfunction "1.47_1.47") (pintype "bidirectional"))
    )
    (net (code "120") (name "unconnected-(H1-Pad1.49)") (class "Default")
      (node (ref "H1") (pin "1.49") (pinfunction "1.49_1.49") (pintype "bidirectional"))
    )
    (net (code "121") (name "unconnected-(H1-Pad1.50)") (class "Default")
      (node (ref "H1") (pin "1.50") (pinfunction "1.50_1.50") (pintype "bidirectional"))
    )
    (net (code "122") (name "unconnected-(H1-Pad1.51)") (class "Default")
      (node (ref "H1") (pin "1.51") (pinfunction "1.51_1.51") (pintype "bidirectional"))
    )
    (net (code "123") (name "unconnected-(H1-Pad1.52)") (class "Default")
      (node (ref "H1") (pin "1.52") (pinfunction "1.52_1.52") (pintype "bidirectional"))
    )
    (net (code "124") (name "unconnected-(H1-Pad2.1)") (class "Default")
      (node (ref "H1") (pin "2.1") (pinfunction "2.1_2.1") (pintype "bidirectional"))
    )
    (net (code "125") (name "unconnected-(H1-Pad2.2)") (class "Default")
      (node (ref "H1") (pin "2.2") (pinfunction "2.2_2.2") (pintype "bidirectional"))
    )
    (net (code "126") (name "unconnected-(H1-Pad2.3)") (class "Default")
      (node (ref "H1") (pin "2.3") (pinfunction "2.3_2.3") (pintype "bidirectional"))
    )
    (net (code "127") (name "unconnected-(H1-Pad2.4)") (class "Default")
      (node (ref "H1") (pin "2.4") (pinfunction "2.4_2.4") (pintype "bidirectional"))
    )
    (net (code "128") (name "unconnected-(H1-Pad2.5)") (class "Default")
      (node (ref "H1") (pin "2.5") (pinfunction "2.5_2.5") (pintype "bidirectional"))
    )
    (net (code "129") (name "unconnected-(H1-Pad2.6)") (class "Default")
      (node (ref "H1") (pin "2.6") (pinfunction "2.6_2.6") (pintype "bidirectional"))
    )
    (net (code "130") (name "unconnected-(H1-Pad2.9)") (class "Default")
      (node (ref "H1") (pin "2.9") (pinfunction "2.9_2.9") (pintype "bidirectional"))
    )
    (net (code "131") (name "unconnected-(H1-Pad2.10)") (class "Default")
      (node (ref "H1") (pin "2.10") (pinfunction "2.10_2.10") (pintype "bidirectional"))
    )
    (net (code "132") (name "unconnected-(H1-Pad2.11)") (class "Default")
      (node (ref "H1") (pin "2.11") (pinfunction "2.11_2.11") (pintype "bidirectional"))
    )
    (net (code "133") (name "unconnected-(H1-Pad2.12)") (class "Default")
      (node (ref "H1") (pin "2.12") (pinfunction "2.12_2.12") (pintype "bidirectional"))
    )
    (net (code "134") (name "unconnected-(H1-Pad2.13)") (class "Default")
      (node (ref "H1") (pin "2.13") (pinfunction "2.13_2.13") (pintype "bidirectional"))
    )
    (net (code "135") (name "unconnected-(H1-Pad2.15)") (class "Default")
      (node (ref "H1") (pin "2.15") (pinfunction "2.15_2.15") (pintype "bidirectional"))
    )
    (net (code "136") (name "unconnected-(H1-Pad2.16)") (class "Default")
      (node (ref "H1") (pin "2.16") (pinfunction "2.16_2.16") (pintype "bidirectional"))
    )
    (net (code "137") (name "unconnected-(H1-Pad2.18)") (class "Default")
      (node (ref "H1") (pin "2.18") (pinfunction "2.18_2.18") (pintype "bidirectional"))
    )
    (net (code "138") (name "unconnected-(H1-Pad2.19)") (class "Default")
      (node (ref "H1") (pin "2.19") (pinfunction "2.19_2.19") (pintype "bidirectional"))
    )
    (net (code "139") (name "unconnected-(H1-Pad2.20)") (class "Default")
      (node (ref "H1") (pin "2.20") (pinfunction "2.20_2.20") (pintype "bidirectional"))
    )
    (net (code "140") (name "unconnected-(H1-Pad2.23)") (class "Default")
      (node (ref "H1") (pin "2.23") (pinfunction "2.23_2.23") (pintype "bidirectional"))
    )
    (net (code "141") (name "unconnected-(H1-Pad2.24)") (class "Default")
      (node (ref "H1") (pin "2.24") (pinfunction "2.24_2.24") (pintype "bidirectional"))
    )
    (net (code "142") (name "unconnected-(H1-Pad2.25)") (class "Default")
      (node (ref "H1") (pin "2.25") (pinfunction "2.25_2.25") (pintype "bidirectional"))
    )
    (net (code "143") (name "unconnected-(H1-Pad2.26)") (class "Default")
      (node (ref "H1") (pin "2.26") (pinfunction "2.26_2.26") (pintype "bidirectional"))
    )
    (net (code "144") (name "unconnected-(H1-Pad2.27)") (class "Default")
      (node (ref "H1") (pin "2.27") (pinfunction "2.27_2.27") (pintype "bidirectional"))
    )
    (net (code "145") (name "unconnected-(H1-Pad2.28)") (class "Default")
      (node (ref "H1") (pin "2.28") (pinfunction "2.28_2.28") (pintype "bidirectional"))
    )
    (net (code "146") (name "unconnected-(H1-Pad2.31)") (class "Default")
      (node (ref "H1") (pin "2.31") (pinfunction "2.31_2.31") (pintype "bidirectional"))
    )
    (net (code "147") (name "unconnected-(H1-Pad2.33)") (class "Default")
      (node (ref "H1") (pin "2.33") (pinfunction "2.33_2.33") (pintype "bidirectional"))
    )
    (net (code "148") (name "unconnected-(H1-Pad2.34)") (class "Default")
      (node (ref "H1") (pin "2.34") (pinfunction "2.34_2.34") (pintype "bidirectional"))
    )
    (net (code "149") (name "unconnected-(H1-Pad2.35)") (class "Default")
      (node (ref "H1") (pin "2.35") (pinfunction "2.35_2.35") (pintype "bidirectional"))
    )
    (net (code "150") (name "unconnected-(H1-Pad2.36)") (class "Default")
      (node (ref "H1") (pin "2.36") (pinfunction "2.36_2.36") (pintype "bidirectional"))
    )
    (net (code "151") (name "unconnected-(H1-Pad2.37)") (class "Default")
      (node (ref "H1") (pin "2.37") (pinfunction "2.37_2.37") (pintype "bidirectional"))
    )
    (net (code "152") (name "unconnected-(H1-Pad2.38)") (class "Default")
      (node (ref "H1") (pin "2.38") (pinfunction "2.38_2.38") (pintype "bidirectional"))
    )
    (net (code "153") (name "unconnected-(H1-Pad2.39)") (class "Default")
      (node (ref "H1") (pin "2.39") (pinfunction "2.39_2.39") (pintype "bidirectional"))
    )
    (net (code "154") (name "unconnected-(H1-Pad2.40)") (class "Default")
      (node (ref "H1") (pin "2.40") (pinfunction "2.40_2.40") (pintype "bidirectional"))
    )
    (net (code "155") (name "unconnected-(H1-Pad2.41)") (class "Default")
      (node (ref "H1") (pin "2.41") (pinfunction "2.41_2.41") (pintype "bidirectional"))
    )
    (net (code "156") (name "unconnected-(H1-Pad2.42)") (class "Default")
      (node (ref "H1") (pin "2.42") (pinfunction "2.42_2.42") (pintype "bidirectional"))
    )
    (net (code "157") (name "unconnected-(H1-Pad2.43)") (class "Default")
      (node (ref "H1") (pin "2.43") (pinfunction "2.43_2.43") (pintype "bidirectional"))
    )
    (net (code "158") (name "unconnected-(H1-Pad2.44)") (class "Default")
      (node (ref "H1") (pin "2.44") (pinfunction "2.44_2.44") (pintype "bidirectional"))
    )
    (net (code "159") (name "unconnected-(H1-Pad2.45)") (class "Default")
      (node (ref "H1") (pin "2.45") (pinfunction "2.45_2.45") (pintype "bidirectional"))
    )
    (net (code "160") (name "unconnected-(H1-Pad2.46)") (class "Default")
      (node (ref "H1") (pin "2.46") (pinfunction "2.46_2.46") (pintype "bidirectional"))
    )
    (net (code "161") (name "unconnected-(H1-Pad2.49)") (class "Default")
      (node (ref "H1") (pin "2.49") (pinfunction "2.49_2.49") (pintype "bidirectional"))
    )
    (net (code "162") (name "unconnected-(H1-Pad2.50)") (class "Default")
      (node (ref "H1") (pin "2.50") (pinfunction "2.50_2.50") (pintype "bidirectional"))
    )
    (net (code "163") (name "unconnected-(H1-Pad2.51)") (class "Default")
      (node (ref "H1") (pin "2.51") (pinfunction "2.51_2.51") (pintype "bidirectional"))
    )
    (net (code "164") (name "unconnected-(H1-Pad2.52)") (class "Default")
      (node (ref "H1") (pin "2.52") (pinfunction "2.52_2.52") (pintype "bidirectional"))
    )
    (net (code "165") (name "unconnected-(H1-PadP$1)") (class "Default")
      (node (ref "H1") (pin "P$1") (pinfunction "P$1_P$1") (pintype "bidirectional"))
    )
    (net (code "166") (name "unconnected-(H1-PadP$2)") (class "Default")
      (node (ref "H1") (pin "P$2") (pinfunction "P$2_P$2") (pintype "bidirectional"))
    )
    (net (code "167") (name "unconnected-(H1-PadP$3)") (class "Default")
      (node (ref "H1") (pin "P$3") (pinfunction "P$3_P$3") (pintype "bidirectional"))
    )
    (net (code "168") (name "unconnected-(P8AB-1-Pad34)") (class "Default")
      (node (ref "P8") (pin "34") (pinfunction "1_34") (pintype "passive"))
    )
    (net (code "169") (name "unconnected-(P8AD-1-Pad36)") (class "Default")
      (node (ref "P8") (pin "36") (pinfunction "1_36") (pintype "passive"))
    )
    (net (code "170") (name "unconnected-(P8AR-1-Pad7)") (class "Default")
      (node (ref "P8") (pin "7") (pinfunction "1_7") (pintype "passive"))
    )
    (net (code "171") (name "unconnected-(P8AS-1-Pad8)") (class "Default")
      (node (ref "P8") (pin "8") (pinfunction "1_8") (pintype "passive"))
    )
    (net (code "172") (name "unconnected-(P8AT-1-Pad9)") (class "Default")
      (node (ref "P8") (pin "9") (pinfunction "1_9") (pintype "passive"))
    )
    (net (code "173") (name "unconnected-(P8B-1-Pad10)") (class "Default")
      (node (ref "P8") (pin "10") (pinfunction "1_10") (pintype "passive"))
    )
    (net (code "174") (name "unconnected-(P8E-1-Pad13)") (class "Default")
      (node (ref "P8") (pin "13") (pinfunction "1_13") (pintype "passive"))
    )
    (net (code "175") (name "unconnected-(P8F-1-Pad14)") (class "Default")
      (node (ref "P8") (pin "14") (pinfunction "1_14") (pintype "passive"))
    )
    (net (code "176") (name "unconnected-(P8K-1-Pad19)") (class "Default")
      (node (ref "P8") (pin "19") (pinfunction "1_19") (pintype "passive"))
    )
    (net (code "177") (name "unconnected-(P8O-1-Pad22)") (class "Default")
      (node (ref "P8") (pin "22") (pinfunction "1_22") (pintype "passive"))
    )
    (net (code "178") (name "unconnected-(P8Y-1-Pad31)") (class "Default")
      (node (ref "P8") (pin "31") (pinfunction "1_31") (pintype "passive"))
    )
    (net (code "179") (name "unconnected-(P8Z-1-Pad32)") (class "Default")
      (node (ref "P8") (pin "32") (pinfunction "1_32") (pintype "passive"))
    )
    (net (code "180") (name "unconnected-(P9AJ-1-Pad41)") (class "Default")
      (node (ref "P9") (pin "41") (pinfunction "1_41") (pintype "passive"))
    )
    (net (code "181") (name "unconnected-(P9AK-1-Pad42)") (class "Default")
      (node (ref "P9") (pin "42") (pinfunction "1_42") (pintype "passive"))
    )
    (net (code "182") (name "unconnected-(P9AL-1-Pad43)") (class "Default")
      (node (ref "P9") (pin "43") (pinfunction "1_43") (pintype "passive"))
    )
    (net (code "183") (name "unconnected-(P9AM-1-Pad44)") (class "Default")
      (node (ref "P9") (pin "44") (pinfunction "1_44") (pintype "passive"))
    )
    (net (code "184") (name "unconnected-(P9AN-1-Pad45)") (class "Default")
      (node (ref "P9") (pin "45") (pinfunction "1_45") (pintype "passive"))
    )
    (net (code "185") (name "unconnected-(P9AO-1-Pad46)") (class "Default")
      (node (ref "P9") (pin "46") (pinfunction "1_46") (pintype "passive"))
    )
    (net (code "186") (name "unconnected-(P9AR-1-Pad7)") (class "Default")
      (node (ref "P9") (pin "7") (pinfunction "1_7") (pintype "passive"))
    )
    (net (code "187") (name "unconnected-(P9AS-1-Pad8)") (class "Default")
      (node (ref "P9") (pin "8") (pinfunction "1_8") (pintype "passive"))
    )
    (net (code "188") (name "unconnected-(P9AT-1-Pad9)") (class "Default")
      (node (ref "P9") (pin "9") (pinfunction "1_9") (pintype "passive"))
    )
    (net (code "189") (name "unconnected-(P9C-1-Pad11)") (class "Default")
      (node (ref "P9") (pin "11") (pinfunction "1_11") (pintype "passive"))
    )
    (net (code "190") (name "unconnected-(P9E-1-Pad13)") (class "Default")
      (node (ref "P9") (pin "13") (pinfunction "1_13") (pintype "passive"))
    )
    (net (code "191") (name "unconnected-(P9F-1-Pad14)") (class "Default")
      (node (ref "P9") (pin "14") (pinfunction "1_14") (pintype "passive"))
    )
    (net (code "192") (name "unconnected-(P9H-1-Pad16)") (class "Default")
      (node (ref "P9") (pin "16") (pinfunction "1_16") (pintype "passive"))
    )
    (net (code "193") (name "unconnected-(P9Z-1-Pad32)") (class "Default")
      (node (ref "P9") (pin "32") (pinfunction "1_32") (pintype "passive"))
    )
    (net (code "194") (name "unconnected-(U3-AIN1{slash}VREF-Pad4)") (class "Default")
      (node (ref "U3") (pin "4") (pinfunction "AIN1/VREF_4") (pintype "passive"))
    )
  )
)
